# qfn-10-socket-pcb-mk-1_0_0.net
KiCad netlist of a schematic drawn in EAGLE
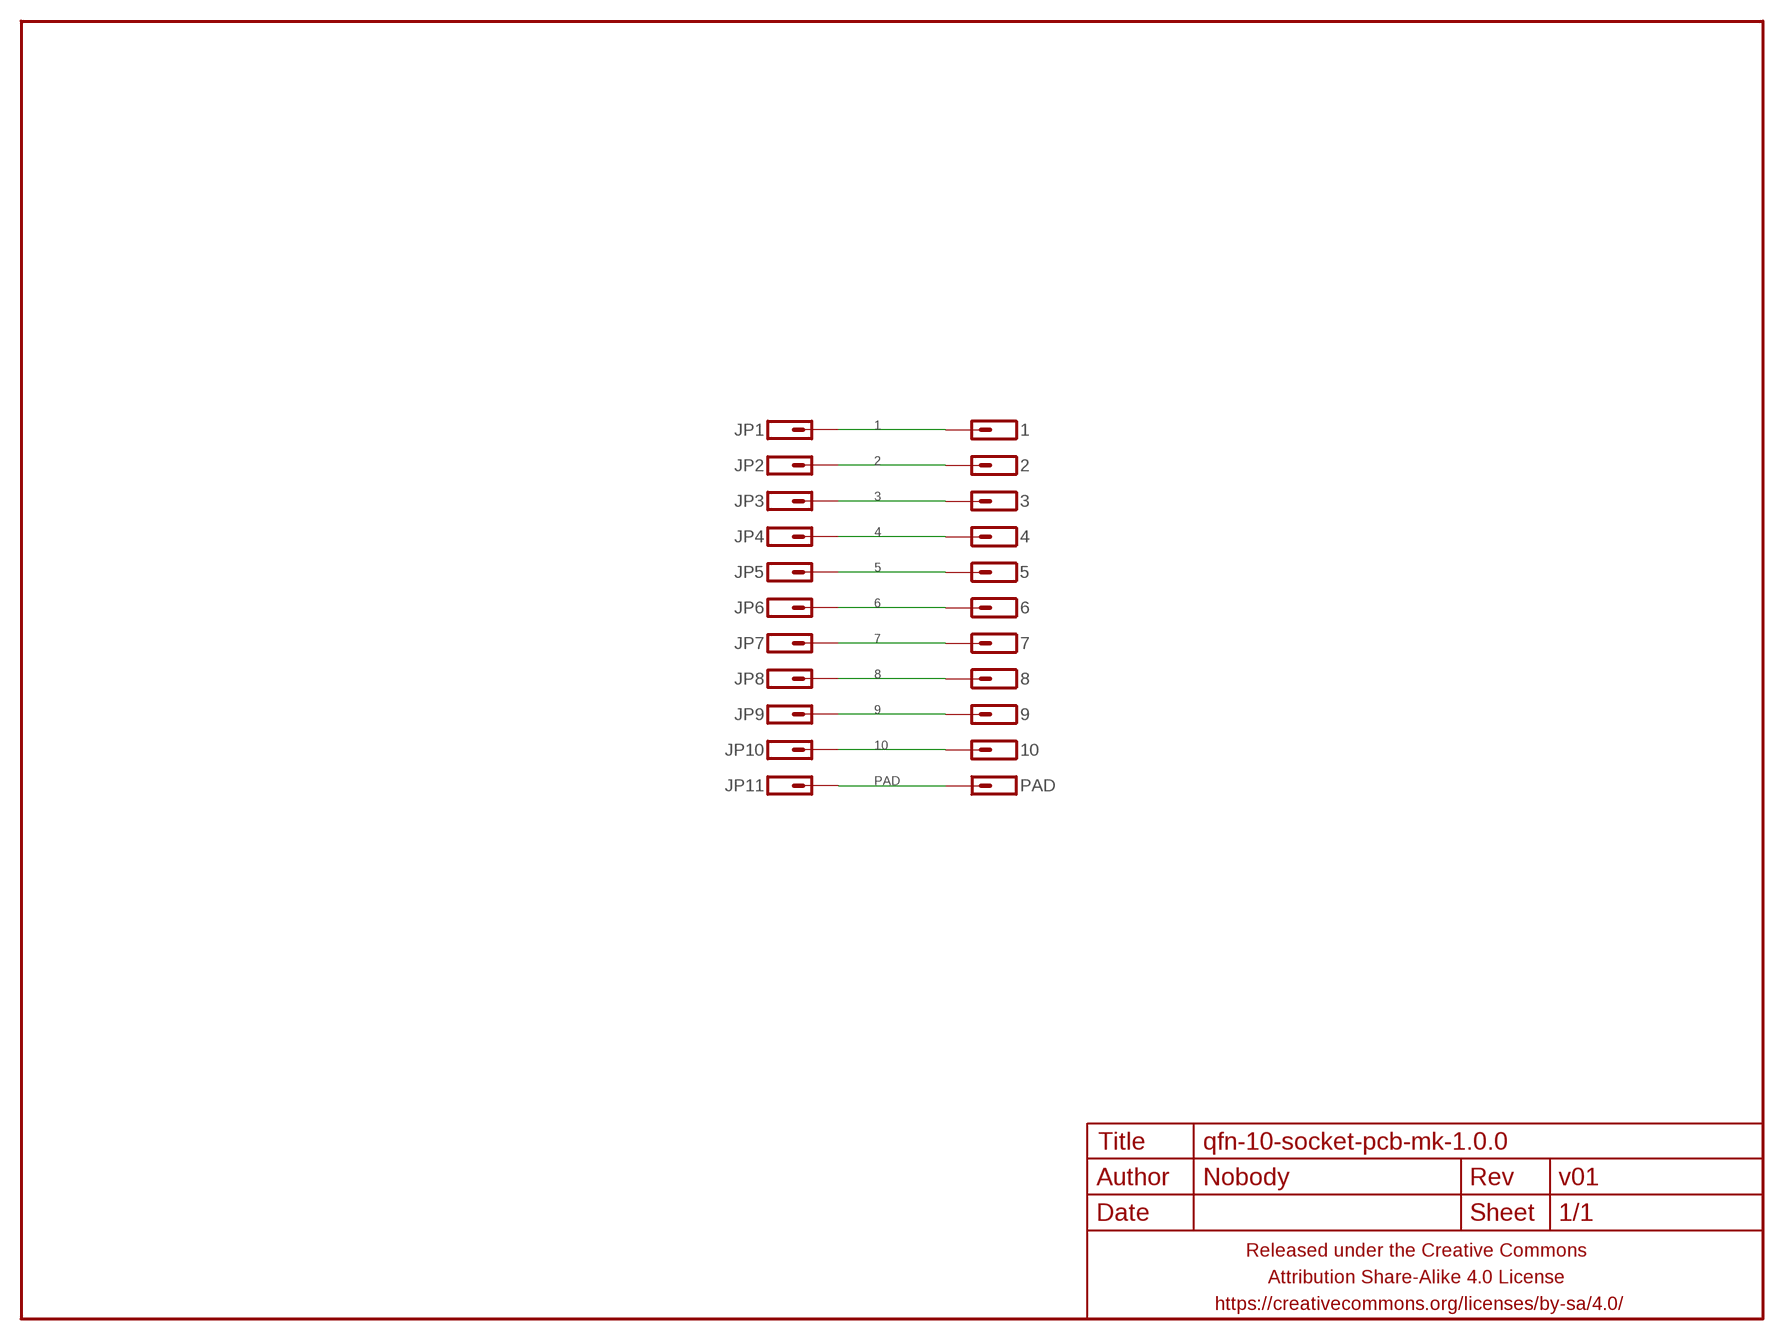
[diagram p0: schematic, sheet 1]

(export (version "E")
  (design (tool "Eeschema 10.0.6"))
  (components
    (comp (ref "1")
      (value "M01PTH")
      (footprint "eagle-import:1X01")
      (libsource (lib "eagle-import") (part "M01PTH"))
    )
    (comp (ref "2")
      (value "M01PTH")
      (footprint "eagle-import:1X01")
      (libsource (lib "eagle-import") (part "M01PTH"))
    )
    (comp (ref "3")
      (value "M01PTH")
      (footprint "eagle-import:1X01")
      (libsource (lib "eagle-import") (part "M01PTH"))
    )
    (comp (ref "4")
      (value "M01PTH")
      (footprint "eagle-import:1X01")
      (libsource (lib "eagle-import") (part "M01PTH"))
    )
    (comp (ref "5")
      (value "M01PTH")
      (footprint "eagle-import:1X01")
      (libsource (lib "eagle-import") (part "M01PTH"))
    )
    (comp (ref "6")
      (value "M01PTH")
      (footprint "eagle-import:1X01")
      (libsource (lib "eagle-import") (part "M01PTH"))
    )
    (comp (ref "7")
      (value "M01PTH")
      (footprint "eagle-import:1X01")
      (libsource (lib "eagle-import") (part "M01PTH"))
    )
    (comp (ref "8")
      (value "M01PTH")
      (footprint "eagle-import:1X01")
      (libsource (lib "eagle-import") (part "M01PTH"))
    )
    (comp (ref "9")
      (value "M01PTH")
      (footprint "eagle-import:1X01")
      (libsource (lib "eagle-import") (part "M01PTH"))
    )
    (comp (ref "10")
      (value "M01PTH")
      (footprint "eagle-import:1X01")
      (libsource (lib "eagle-import") (part "M01PTH"))
    )
    (comp (ref "FRAME1")
      (value "FRAME-LETTERNO_PACKAGE")
      (footprint "eagle-import:DUMMY")
      (fields (field (name "DESIGNER") "Nobody") (field (name "VERSION") "v01"))
      (libsource (lib "eagle-import") (part "FRAME-LETTERNO_PACKAGE"))
    )
    (comp (ref "JP1")
      (value "M01PTH-0.4MM")
      (footprint "eagle-import:1X01-0.4MM")
      (libsource (lib "eagle-import") (part "M01PTH-0.4MM"))
    )
    (comp (ref "JP2")
      (value "M01PTH-0.4MM")
      (footprint "eagle-import:1X01-0.4MM")
      (libsource (lib "eagle-import") (part "M01PTH-0.4MM"))
    )
    (comp (ref "JP3")
      (value "M01PTH-0.4MM")
      (footprint "eagle-import:1X01-0.4MM")
      (libsource (lib "eagle-import") (part "M01PTH-0.4MM"))
    )
    (comp (ref "JP4")
      (value "M01PTH-0.4MM")
      (footprint "eagle-import:1X01-0.4MM")
      (libsource (lib "eagle-import") (part "M01PTH-0.4MM"))
    )
    (comp (ref "JP5")
      (value "M01PTH-0.4MM")
      (footprint "eagle-import:1X01-0.4MM")
      (libsource (lib "eagle-import") (part "M01PTH-0.4MM"))
    )
    (comp (ref "JP6")
      (value "M01PTH-0.4MM")
      (footprint "eagle-import:1X01-0.4MM")
      (libsource (lib "eagle-import") (part "M01PTH-0.4MM"))
    )
    (comp (ref "JP7")
      (value "M01PTH-0.4MM")
      (footprint "eagle-import:1X01-0.4MM")
      (libsource (lib "eagle-import") (part "M01PTH-0.4MM"))
    )
    (comp (ref "JP8")
      (value "M01PTH-0.4MM")
      (footprint "eagle-import:1X01-0.4MM")
      (libsource (lib "eagle-import") (part "M01PTH-0.4MM"))
    )
    (comp (ref "JP9")
      (value "M01PTH-0.4MM")
      (footprint "eagle-import:1X01-0.4MM")
      (libsource (lib "eagle-import") (part "M01PTH-0.4MM"))
    )
    (comp (ref "JP10")
      (value "M01PTH-0.4MM")
      (footprint "eagle-import:1X01-0.4MM")
      (libsource (lib "eagle-import") (part "M01PTH-0.4MM"))
    )
    (comp (ref "JP11")
      (value "M01PTH")
      (footprint "eagle-import:1X01")
      (libsource (lib "eagle-import") (part "M01PTH"))
    )
    (comp (ref "PAD")
      (value "M01PTH-3.3MM")
      (footprint "eagle-import:1X01-3.3MM")
      (libsource (lib "eagle-import") (part "M01PTH-3.3MM"))
    )
  )
  (nets
    (net (code "1") (name "/1") (class "Default")
      (node (ref "1") (pin "1") (pinfunction "1_1") (pintype "passive"))
      (node (ref "JP1") (pin "P$1") (pinfunction "1_P$1") (pintype "passive"))
    )
    (net (code "2") (name "/2") (class "Default")
      (node (ref "2") (pin "1") (pinfunction "1_1") (pintype "passive"))
      (node (ref "JP2") (pin "P$1") (pinfunction "1_P$1") (pintype "passive"))
    )
    (net (code "3") (name "/3") (class "Default")
      (node (ref "3") (pin "1") (pinfunction "1_1") (pintype "passive"))
      (node (ref "JP3") (pin "P$1") (pinfunction "1_P$1") (pintype "passive"))
    )
    (net (code "4") (name "/4") (class "Default")
      (node (ref "4") (pin "1") (pinfunction "1_1") (pintype "passive"))
      (node (ref "JP4") (pin "P$1") (pinfunction "1_P$1") (pintype "passive"))
    )
    (net (code "5") (name "/5") (class "Default")
      (node (ref "5") (pin "1") (pinfunction "1_1") (pintype "passive"))
      (node (ref "JP5") (pin "P$1") (pinfunction "1_P$1") (pintype "passive"))
    )
    (net (code "6") (name "/6") (class "Default")
      (node (ref "6") (pin "1") (pinfunction "1_1") (pintype "passive"))
      (node (ref "JP6") (pin "P$1") (pinfunction "1_P$1") (pintype "passive"))
    )
    (net (code "7") (name "/7") (class "Default")
      (node (ref "7") (pin "1") (pinfunction "1_1") (pintype "passive"))
      (node (ref "JP7") (pin "P$1") (pinfunction "1_P$1") (pintype "passive"))
    )
    (net (code "8") (name "/8") (class "Default")
      (node (ref "8") (pin "1") (pinfunction "1_1") (pintype "passive"))
      (node (ref "JP8") (pin "P$1") (pinfunction "1_P$1") (pintype "passive"))
    )
    (net (code "9") (name "/9") (class "Default")
      (node (ref "9") (pin "1") (pinfunction "1_1") (pintype "passive"))
      (node (ref "JP9") (pin "P$1") (pinfunction "1_P$1") (pintype "passive"))
    )
    (net (code "10") (name "/10") (class "Default")
      (node (ref "10") (pin "1") (pinfunction "1_1") (pintype "passive"))
      (node (ref "JP10") (pin "P$1") (pinfunction "1_P$1") (pintype "passive"))
    )
    (net (code "11") (name "/PAD") (class "Default")
      (node (ref "JP11") (pin "1") (pinfunction "1_1") (pintype "passive"))
      (node (ref "PAD") (pin "P$1") (pinfunction "1_P$1") (pintype "passive"))
    )
  )
)
